# Dischargers.net
KiCad netlist of a schematic drawn in Altium Designer
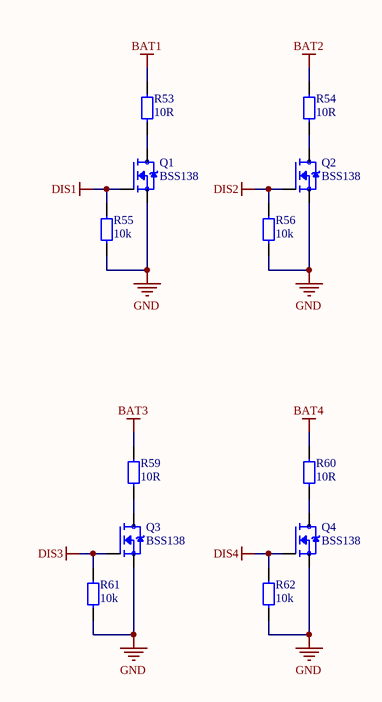
[diagram p0: Dischargers.SchDoc]

(export (version "E")
  (design (tool "Eeschema 10.0.6"))
  (components
    (comp (ref "Q1")
      (value "BSS138")
      (footprint "TRANS_SS8050-G")
      (description "N-Channel 50 V 220mA (Ta) 350mW (Ta) Surface Mount SOT-23-3")
      (fields (field (name "MF") "onsemi"))
      (libsource (lib "Transistor") (part "BSS138"))
    )
    (comp (ref "Q2")
      (value "BSS138")
      (footprint "TRANS_SS8050-G")
      (description "N-Channel 50 V 220mA (Ta) 350mW (Ta) Surface Mount SOT-23-3")
      (fields (field (name "MF") "onsemi"))
      (libsource (lib "Transistor") (part "BSS138"))
    )
    (comp (ref "Q3")
      (value "BSS138")
      (footprint "TRANS_SS8050-G")
      (description "N-Channel 50 V 220mA (Ta) 350mW (Ta) Surface Mount SOT-23-3")
      (fields (field (name "MF") "onsemi"))
      (libsource (lib "Transistor") (part "BSS138"))
    )
    (comp (ref "Q4")
      (value "BSS138")
      (footprint "TRANS_SS8050-G")
      (description "N-Channel 50 V 220mA (Ta) 350mW (Ta) Surface Mount SOT-23-3")
      (fields (field (name "MF") "onsemi"))
      (libsource (lib "Transistor") (part "BSS138"))
    )
    (comp (ref "R53")
      (value "10R")
      (footprint "THT 3W resistor")
      (description "15R 3W THT")
      (libsource (lib "Resistors") (part "15R 3W THT"))
    )
    (comp (ref "R54")
      (value "10R")
      (footprint "THT 3W resistor")
      (description "15R 3W THT")
      (libsource (lib "Resistors") (part "15R 3W THT"))
    )
    (comp (ref "R55")
      (value "10k")
      (footprint "0603 Resistor")
      (description "10k 0603")
      (fields (field (name "Comment") "Resistor 10k 0603"))
      (libsource (lib "KamaratiVUT") (part "Resistor 1R5 1R5 0603"))
    )
    (comp (ref "R56")
      (value "10k")
      (footprint "0603 Resistor")
      (description "10k 0603")
      (fields (field (name "Comment") "Resistor 10k 0603"))
      (libsource (lib "KamaratiVUT") (part "Resistor 1R5 1R5 0603"))
    )
    (comp (ref "R59")
      (value "10R")
      (footprint "THT 3W resistor")
      (description "15R 3W THT")
      (libsource (lib "Resistors") (part "15R 3W THT"))
    )
    (comp (ref "R60")
      (value "10R")
      (footprint "THT 3W resistor")
      (description "15R 3W THT")
      (libsource (lib "Resistors") (part "15R 3W THT"))
    )
    (comp (ref "R61")
      (value "10k")
      (footprint "0603 Resistor")
      (description "10k 0603")
      (fields (field (name "Comment") "Resistor 10k 0603"))
      (libsource (lib "KamaratiVUT") (part "Resistor 1R5 1R5 0603"))
    )
    (comp (ref "R62")
      (value "10k")
      (footprint "0603 Resistor")
      (description "10k 0603")
      (fields (field (name "Comment") "Resistor 10k 0603"))
      (libsource (lib "KamaratiVUT") (part "Resistor 1R5 1R5 0603"))
    )
  )
  (nets
    (net (code "1") (name "BAT1") (class "Default")
      (node (ref "R53") (pin "2") (pinfunction "CW_2") (pintype "passive"))
    )
    (net (code "2") (name "BAT2") (class "Default")
      (node (ref "R54") (pin "2") (pinfunction "CW_2") (pintype "passive"))
    )
    (net (code "3") (name "BAT3") (class "Default")
      (node (ref "R59") (pin "2") (pinfunction "CW_2") (pintype "passive"))
    )
    (net (code "4") (name "BAT4") (class "Default")
      (node (ref "R60") (pin "2") (pinfunction "CW_2") (pintype "passive"))
    )
    (net (code "5") (name "DIS1") (class "Default")
      (node (ref "Q1") (pin "1") (pinfunction "G_1") (pintype "passive"))
      (node (ref "R55") (pin "1") (pinfunction "CCW_1") (pintype "passive"))
    )
    (net (code "6") (name "DIS2") (class "Default")
      (node (ref "Q2") (pin "1") (pinfunction "G_1") (pintype "passive"))
      (node (ref "R56") (pin "1") (pinfunction "CCW_1") (pintype "passive"))
    )
    (net (code "7") (name "DIS3") (class "Default")
      (node (ref "Q3") (pin "1") (pinfunction "G_1") (pintype "passive"))
      (node (ref "R61") (pin "1") (pinfunction "CCW_1") (pintype "passive"))
    )
    (net (code "8") (name "DIS4") (class "Default")
      (node (ref "Q4") (pin "1") (pinfunction "G_1") (pintype "passive"))
      (node (ref "R62") (pin "1") (pinfunction "CCW_1") (pintype "passive"))
    )
    (net (code "9") (name "GND") (class "Default")
      (node (ref "Q1") (pin "2") (pinfunction "S_2") (pintype "passive"))
      (node (ref "Q2") (pin "2") (pinfunction "S_2") (pintype "passive"))
      (node (ref "Q3") (pin "2") (pinfunction "S_2") (pintype "passive"))
      (node (ref "Q4") (pin "2") (pinfunction "S_2") (pintype "passive"))
      (node (ref "R55") (pin "2") (pinfunction "CW_2") (pintype "passive"))
      (node (ref "R56") (pin "2") (pinfunction "CW_2") (pintype "passive"))
      (node (ref "R61") (pin "2") (pinfunction "CW_2") (pintype "passive"))
      (node (ref "R62") (pin "2") (pinfunction "CW_2") (pintype "passive"))
    )
    (net (code "10") (name "Net-(Q1-D)") (class "Default")
      (node (ref "Q1") (pin "3") (pinfunction "D_3") (pintype "passive"))
      (node (ref "R53") (pin "1") (pinfunction "CCW_1") (pintype "passive"))
    )
    (net (code "11") (name "Net-(Q2-D)") (class "Default")
      (node (ref "Q2") (pin "3") (pinfunction "D_3") (pintype "passive"))
      (node (ref "R54") (pin "1") (pinfunction "CCW_1") (pintype "passive"))
    )
    (net (code "12") (name "Net-(Q3-D)") (class "Default")
      (node (ref "Q3") (pin "3") (pinfunction "D_3") (pintype "passive"))
      (node (ref "R59") (pin "1") (pinfunction "CCW_1") (pintype "passive"))
    )
    (net (code "13") (name "Net-(Q4-D)") (class "Default")
      (node (ref "Q4") (pin "3") (pinfunction "D_3") (pintype "passive"))
      (node (ref "R60") (pin "1") (pinfunction "CCW_1") (pintype "passive"))
    )
  )
)
